# Warmie_Helper_Board_V_9.net
KiCad netlist of a schematic drawn in EAGLE
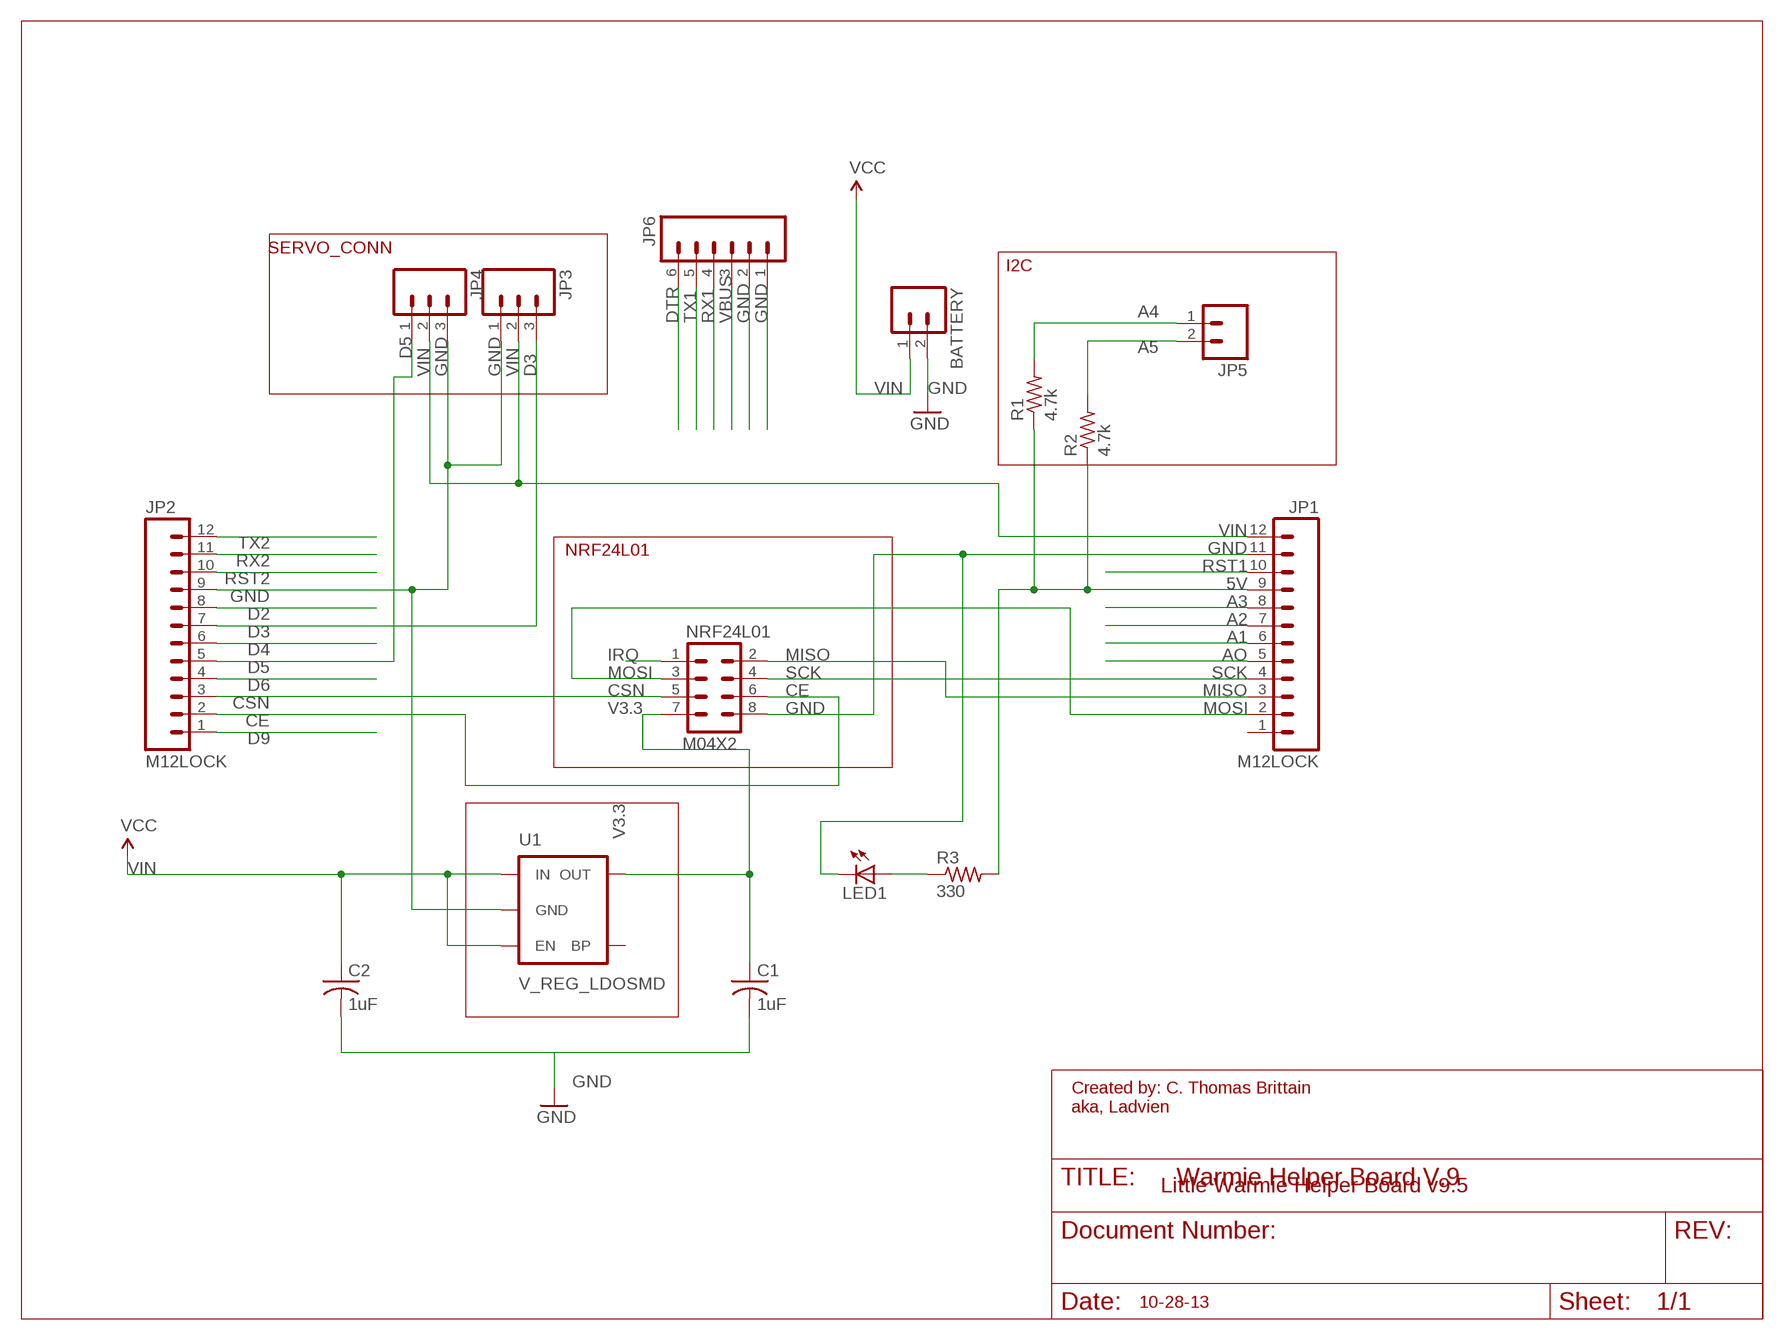
[diagram p0: schematic, sheet 1]

(export (version "E")
  (design (tool "Eeschema 10.0.6"))
  (components
    (comp (ref "BATTERY")
      (value "M02LOCK")
      (footprint "eagle-import:1X02_LOCK")
      (libsource (lib "eagle-import") (part "M02LOCK"))
    )
    (comp (ref "C1")
      (value "1uF")
      (footprint "eagle-import:C0805")
      (libsource (lib "eagle-import") (part "C-USC0805"))
    )
    (comp (ref "C2")
      (value "1uF")
      (footprint "eagle-import:C0805")
      (libsource (lib "eagle-import") (part "C-USC0805"))
    )
    (comp (ref "JP1")
      (value "M12LOCK")
      (footprint "eagle-import:1X12_LOCK")
      (libsource (lib "eagle-import") (part "M12LOCK"))
    )
    (comp (ref "JP2")
      (value "M12LOCK")
      (footprint "eagle-import:1X12_LOCK")
      (libsource (lib "eagle-import") (part "M12LOCK"))
    )
    (comp (ref "JP3")
      (value "M03LOCK")
      (footprint "eagle-import:1X03_LOCK")
      (libsource (lib "eagle-import") (part "M03LOCK"))
    )
    (comp (ref "JP4")
      (value "M03LOCK")
      (footprint "eagle-import:1X03_LOCK")
      (libsource (lib "eagle-import") (part "M03LOCK"))
    )
    (comp (ref "JP5")
      (value "M02LOCK")
      (footprint "eagle-import:1X02_LOCK")
      (libsource (lib "eagle-import") (part "M02LOCK"))
    )
    (comp (ref "JP6")
      (value "M06LOCK")
      (footprint "eagle-import:1X06_LOCK")
      (libsource (lib "eagle-import") (part "M06LOCK"))
    )
    (comp (ref "LED1")
      (value "LEDSML0603")
      (footprint "eagle-import:SML0603")
      (libsource (lib "eagle-import") (part "LEDSML0603"))
    )
    (comp (ref "NRF24L01")
      (value "M04X2")
      (footprint "eagle-import:2X4")
      (libsource (lib "eagle-import") (part "M04X2"))
    )
    (comp (ref "R1")
      (value "4.7k")
      (footprint "eagle-import:M0805")
      (libsource (lib "eagle-import") (part "R-US_M0805"))
    )
    (comp (ref "R2")
      (value "4.7k")
      (footprint "eagle-import:M0805")
      (libsource (lib "eagle-import") (part "R-US_M0805"))
    )
    (comp (ref "R3")
      (value "330")
      (footprint "eagle-import:M0805")
      (libsource (lib "eagle-import") (part "R-US_M0805"))
    )
    (comp (ref "U1")
      (value "V_REG_LDOSMD")
      (footprint "eagle-import:SOT23-5")
      (libsource (lib "eagle-import") (part "V_REG_LDOSMD"))
    )
  )
  (nets
    (net (code "1") (name "/5V") (class "Default")
      (node (ref "JP1") (pin "9") (pinfunction "9_9") (pintype "passive"))
      (node (ref "R1") (pin "1") (pinfunction "1_1") (pintype "passive"))
      (node (ref "R2") (pin "1") (pinfunction "1_1") (pintype "passive"))
      (node (ref "R3") (pin "2") (pinfunction "2_2") (pintype "passive"))
    )
    (net (code "2") (name "/A1") (class "Default")
      (node (ref "JP1") (pin "6") (pinfunction "6_6") (pintype "passive"))
    )
    (net (code "3") (name "/A2") (class "Default")
      (node (ref "JP1") (pin "7") (pinfunction "7_7") (pintype "passive"))
    )
    (net (code "4") (name "/A3") (class "Default")
      (node (ref "JP1") (pin "8") (pinfunction "8_8") (pintype "passive"))
    )
    (net (code "5") (name "/A4") (class "Default")
      (node (ref "JP5") (pin "1") (pinfunction "1_1") (pintype "passive"))
      (node (ref "R1") (pin "2") (pinfunction "2_2") (pintype "passive"))
    )
    (net (code "6") (name "/A5") (class "Default")
      (node (ref "JP5") (pin "2") (pinfunction "2_2") (pintype "passive"))
      (node (ref "R2") (pin "2") (pinfunction "2_2") (pintype "passive"))
    )
    (net (code "7") (name "/AO") (class "Default")
      (node (ref "JP1") (pin "5") (pinfunction "5_5") (pintype "passive"))
    )
    (net (code "8") (name "/CE") (class "Default")
      (node (ref "JP2") (pin "2") (pinfunction "2_2") (pintype "passive"))
      (node (ref "NRF24L01") (pin "6") (pinfunction "6_6") (pintype "passive"))
    )
    (net (code "9") (name "/CSN") (class "Default")
      (node (ref "JP2") (pin "3") (pinfunction "3_3") (pintype "passive"))
      (node (ref "NRF24L01") (pin "5") (pinfunction "5_5") (pintype "passive"))
    )
    (net (code "10") (name "/D2") (class "Default")
      (node (ref "JP2") (pin "8") (pinfunction "8_8") (pintype "passive"))
    )
    (net (code "11") (name "/D3") (class "Default")
      (node (ref "JP2") (pin "7") (pinfunction "7_7") (pintype "passive"))
      (node (ref "JP3") (pin "3") (pinfunction "3_3") (pintype "passive"))
    )
    (net (code "12") (name "/D4") (class "Default")
      (node (ref "JP2") (pin "6") (pinfunction "6_6") (pintype "passive"))
    )
    (net (code "13") (name "/D5") (class "Default")
      (node (ref "JP2") (pin "5") (pinfunction "5_5") (pintype "passive"))
      (node (ref "JP4") (pin "1") (pinfunction "1_1") (pintype "passive"))
    )
    (net (code "14") (name "/D6") (class "Default")
      (node (ref "JP2") (pin "4") (pinfunction "4_4") (pintype "passive"))
    )
    (net (code "15") (name "/D9") (class "Default")
      (node (ref "JP2") (pin "1") (pinfunction "1_1") (pintype "passive"))
    )
    (net (code "16") (name "/DTR") (class "Default")
      (node (ref "JP6") (pin "6") (pinfunction "6_6") (pintype "passive"))
    )
    (net (code "17") (name "/IRQ") (class "Default")
      (node (ref "NRF24L01") (pin "1") (pinfunction "1_1") (pintype "passive"))
    )
    (net (code "18") (name "/MISO") (class "Default")
      (node (ref "JP1") (pin "3") (pinfunction "3_3") (pintype "passive"))
      (node (ref "NRF24L01") (pin "2") (pinfunction "2_2") (pintype "passive"))
    )
    (net (code "19") (name "/MOSI") (class "Default")
      (node (ref "JP1") (pin "2") (pinfunction "2_2") (pintype "passive"))
      (node (ref "NRF24L01") (pin "3") (pinfunction "3_3") (pintype "passive"))
    )
    (net (code "20") (name "/RST1") (class "Default")
      (node (ref "JP1") (pin "10") (pinfunction "10_10") (pintype "passive"))
    )
    (net (code "21") (name "/RST2") (class "Default")
      (node (ref "JP2") (pin "10") (pinfunction "10_10") (pintype "passive"))
    )
    (net (code "22") (name "/RX1") (class "Default")
      (node (ref "JP6") (pin "4") (pinfunction "4_4") (pintype "passive"))
    )
    (net (code "23") (name "/RX2") (class "Default")
      (node (ref "JP2") (pin "11") (pinfunction "11_11") (pintype "passive"))
    )
    (net (code "24") (name "/SCK") (class "Default")
      (node (ref "JP1") (pin "4") (pinfunction "4_4") (pintype "passive"))
      (node (ref "NRF24L01") (pin "4") (pinfunction "4_4") (pintype "passive"))
    )
    (net (code "25") (name "/TX1") (class "Default")
      (node (ref "JP6") (pin "5") (pinfunction "5_5") (pintype "passive"))
    )
    (net (code "26") (name "/TX2") (class "Default")
      (node (ref "JP2") (pin "12") (pinfunction "12_12") (pintype "passive"))
    )
    (net (code "27") (name "/V3.3") (class "Default")
      (node (ref "C1") (pin "1") (pinfunction "1_1") (pintype "passive"))
      (node (ref "NRF24L01") (pin "7") (pinfunction "7_7") (pintype "passive"))
      (node (ref "U1") (pin "5") (pinfunction "OUT_5") (pintype "passive"))
    )
    (net (code "28") (name "/VBUS") (class "Default")
      (node (ref "JP6") (pin "3") (pinfunction "3_3") (pintype "passive"))
    )
    (net (code "29") (name "GND") (class "Default")
      (node (ref "BATTERY") (pin "2") (pinfunction "2_2") (pintype "passive"))
      (node (ref "C1") (pin "2") (pinfunction "2_2") (pintype "passive"))
      (node (ref "C2") (pin "2") (pinfunction "2_2") (pintype "passive"))
      (node (ref "JP1") (pin "11") (pinfunction "11_11") (pintype "passive"))
      (node (ref "JP2") (pin "9") (pinfunction "9_9") (pintype "passive"))
      (node (ref "JP3") (pin "1") (pinfunction "1_1") (pintype "passive"))
      (node (ref "JP4") (pin "3") (pinfunction "3_3") (pintype "passive"))
      (node (ref "JP6") (pin "1") (pinfunction "1_1") (pintype "passive"))
      (node (ref "JP6") (pin "2") (pinfunction "2_2") (pintype "passive"))
      (node (ref "LED1") (pin "C") (pinfunction "C_C") (pintype "passive"))
      (node (ref "NRF24L01") (pin "8") (pinfunction "8_8") (pintype "passive"))
      (node (ref "U1") (pin "2") (pinfunction "GND_2") (pintype "input"))
    )
    (net (code "30") (name "Net-(LED1-PadA)") (class "Default")
      (node (ref "LED1") (pin "A") (pinfunction "A_A") (pintype "passive"))
      (node (ref "R3") (pin "1") (pinfunction "1_1") (pintype "passive"))
    )
    (net (code "31") (name "VCC") (class "Default")
      (node (ref "BATTERY") (pin "1") (pinfunction "1_1") (pintype "passive"))
      (node (ref "C2") (pin "1") (pinfunction "1_1") (pintype "passive"))
      (node (ref "JP1") (pin "12") (pinfunction "12_12") (pintype "passive"))
      (node (ref "JP3") (pin "2") (pinfunction "2_2") (pintype "passive"))
      (node (ref "JP4") (pin "2") (pinfunction "2_2") (pintype "passive"))
      (node (ref "U1") (pin "1") (pinfunction "IN_1") (pintype "input"))
      (node (ref "U1") (pin "3") (pinfunction "EN_3") (pintype "input"))
    )
    (net (code "32") (name "unconnected-(JP1-Pad1)") (class "Default")
      (node (ref "JP1") (pin "1") (pinfunction "1_1") (pintype "passive"))
    )
    (net (code "33") (name "unconnected-(U1-BP-Pad4)") (class "Default")
      (node (ref "U1") (pin "4") (pinfunction "BP_4") (pintype "input"))
    )
  )
)
